# momav_imu.net
KiCad netlist of a schematic drawn in EAGLE
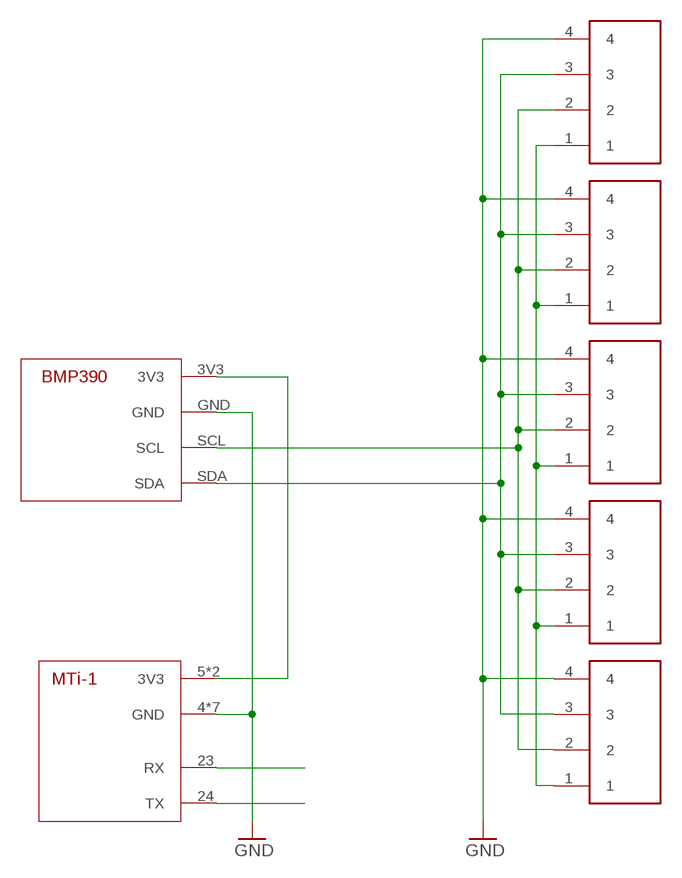
[diagram p0: schematic, sheet 1]

(export (version "E")
  (design (tool "Eeschema 10.0.6"))
  (components
    (comp (ref "U$1")
      (value "JST_ZH_4P")
      (footprint "eagle-import:JST_ZH_4P")
      (libsource (lib "eagle-import") (part "JST_ZH_4P"))
    )
    (comp (ref "U$2")
      (value "JST_ZH_4P")
      (footprint "eagle-import:JST_ZH_4P")
      (libsource (lib "eagle-import") (part "JST_ZH_4P"))
    )
    (comp (ref "U$3")
      (value "JST_ZH_4P")
      (footprint "eagle-import:JST_ZH_4P")
      (libsource (lib "eagle-import") (part "JST_ZH_4P"))
    )
    (comp (ref "U$4")
      (value "JST_ZH_4P")
      (footprint "eagle-import:JST_ZH_4P")
      (libsource (lib "eagle-import") (part "JST_ZH_4P"))
    )
    (comp (ref "U$5")
      (value "JST_ZH_4P")
      (footprint "eagle-import:JST_ZH_4P")
      (libsource (lib "eagle-import") (part "JST_ZH_4P"))
    )
    (comp (ref "U$6")
      (value "XSENS_MTI_1")
      (footprint "eagle-import:XSENS_MTI_1")
      (libsource (lib "eagle-import") (part "XSENS_MTI_1"))
    )
    (comp (ref "U$7")
      (value "BMP390")
      (footprint "eagle-import:BMP390")
      (libsource (lib "eagle-import") (part "BMP390"))
    )
  )
  (nets
    (net (code "1") (name "GND") (class "Default")
      (node (ref "U$1") (pin "4") (pinfunction "4_4") (pintype "bidirectional"))
      (node (ref "U$2") (pin "4") (pinfunction "4_4") (pintype "bidirectional"))
      (node (ref "U$3") (pin "4") (pinfunction "4_4") (pintype "bidirectional"))
      (node (ref "U$4") (pin "4") (pinfunction "4_4") (pintype "bidirectional"))
      (node (ref "U$5") (pin "4") (pinfunction "4_4") (pintype "bidirectional"))
      (node (ref "U$6") (pin "13") (pinfunction "GND_13") (pintype "bidirectional"))
      (node (ref "U$6") (pin "14") (pinfunction "GND_14") (pintype "bidirectional"))
      (node (ref "U$6") (pin "15") (pinfunction "GND_15") (pintype "bidirectional"))
      (node (ref "U$6") (pin "22") (pinfunction "GND_22") (pintype "bidirectional"))
      (node (ref "U$6") (pin "25") (pinfunction "GND_25") (pintype "bidirectional"))
      (node (ref "U$6") (pin "4") (pinfunction "GND_4") (pintype "bidirectional"))
      (node (ref "U$6") (pin "8") (pinfunction "GND_8") (pintype "bidirectional"))
      (node (ref "U$7") (pin "GND") (pinfunction "GND_GND") (pintype "bidirectional"))
    )
    (net (code "2") (name "Net-(U$1-Pad1)") (class "Default")
      (node (ref "U$1") (pin "1") (pinfunction "1_1") (pintype "bidirectional"))
      (node (ref "U$2") (pin "1") (pinfunction "1_1") (pintype "bidirectional"))
      (node (ref "U$3") (pin "1") (pinfunction "1_1") (pintype "bidirectional"))
      (node (ref "U$4") (pin "1") (pinfunction "1_1") (pintype "bidirectional"))
      (node (ref "U$5") (pin "1") (pinfunction "1_1") (pintype "bidirectional"))
    )
    (net (code "3") (name "Net-(U$1-Pad2)") (class "Default")
      (node (ref "U$1") (pin "2") (pinfunction "2_2") (pintype "bidirectional"))
      (node (ref "U$2") (pin "2") (pinfunction "2_2") (pintype "bidirectional"))
      (node (ref "U$3") (pin "2") (pinfunction "2_2") (pintype "bidirectional"))
      (node (ref "U$4") (pin "2") (pinfunction "2_2") (pintype "bidirectional"))
      (node (ref "U$5") (pin "2") (pinfunction "2_2") (pintype "bidirectional"))
      (node (ref "U$7") (pin "SCL") (pinfunction "SCL_SCL") (pintype "bidirectional"))
    )
    (net (code "4") (name "Net-(U$1-Pad3)") (class "Default")
      (node (ref "U$1") (pin "3") (pinfunction "3_3") (pintype "bidirectional"))
      (node (ref "U$2") (pin "3") (pinfunction "3_3") (pintype "bidirectional"))
      (node (ref "U$3") (pin "3") (pinfunction "3_3") (pintype "bidirectional"))
      (node (ref "U$4") (pin "3") (pinfunction "3_3") (pintype "bidirectional"))
      (node (ref "U$5") (pin "3") (pinfunction "3_3") (pintype "bidirectional"))
      (node (ref "U$7") (pin "SDA") (pinfunction "SDA_SDA") (pintype "bidirectional"))
    )
    (net (code "5") (name "Net-(U$6-3V3-Pad5)") (class "Default")
      (node (ref "U$6") (pin "5") (pinfunction "3V3_5") (pintype "bidirectional"))
      (node (ref "U$6") (pin "7") (pinfunction "3V3_7") (pintype "bidirectional"))
      (node (ref "U$7") (pin "3V3") (pinfunction "3V3_3V3") (pintype "bidirectional"))
    )
    (net (code "6") (name "unconnected-(U$6-RX-Pad23)") (class "Default")
      (node (ref "U$6") (pin "23") (pinfunction "RX_23") (pintype "bidirectional"))
    )
    (net (code "7") (name "unconnected-(U$6-TX-Pad24)") (class "Default")
      (node (ref "U$6") (pin "24") (pinfunction "TX_24") (pintype "bidirectional"))
    )
  )
)
